# 2svd.net
KiCad netlist of a schematic drawn in EAGLE
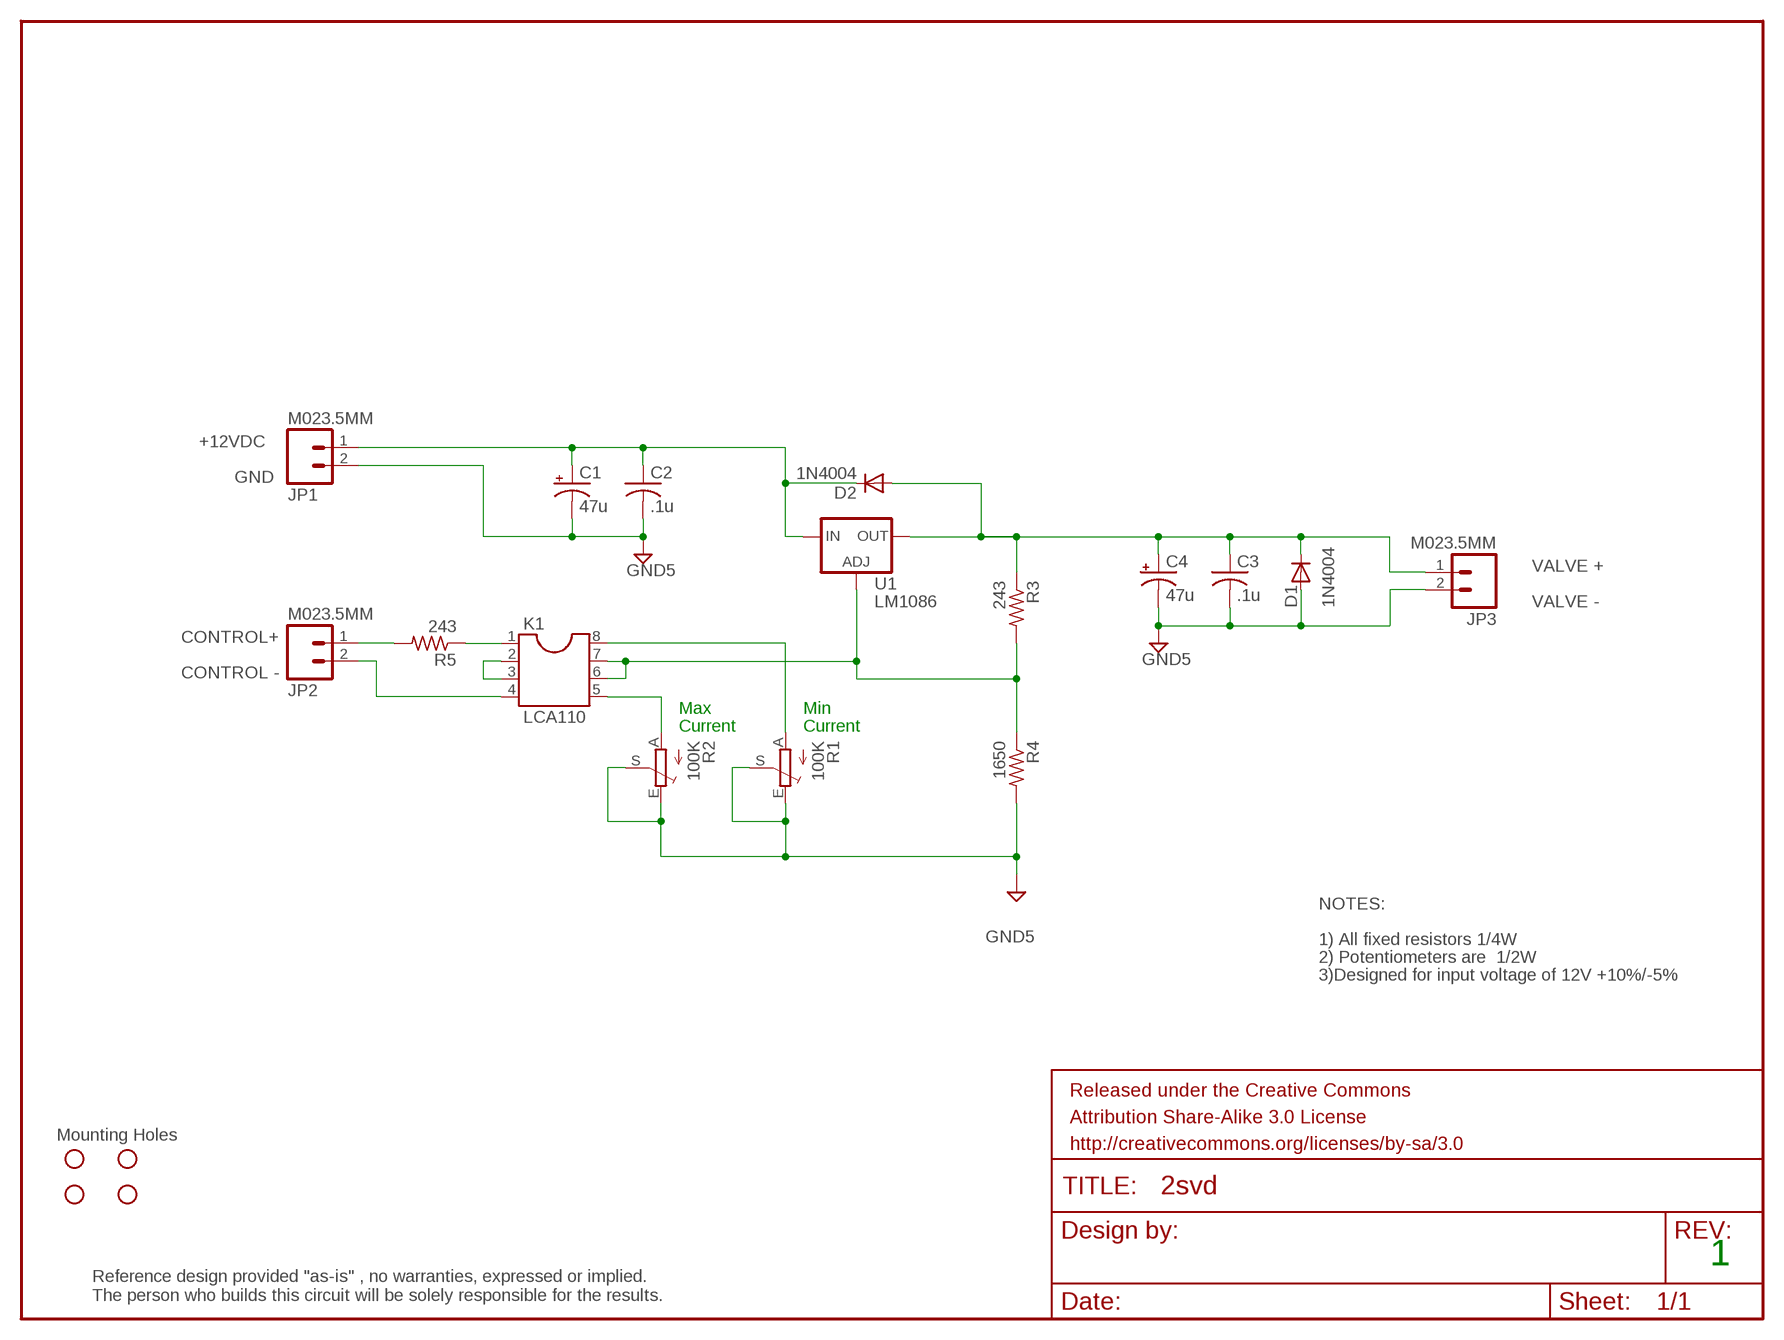
[diagram p0: schematic, sheet 1]

(export (version "E")
  (design (tool "Eeschema 10.0.6"))
  (components
    (comp (ref "C1")
      (value "47u")
      (footprint "eagle-import:CPOL-RADIAL-10UF-25V")
      (libsource (lib "eagle-import") (part "CAP_POLPTH2"))
    )
    (comp (ref "C2")
      (value ".1u")
      (footprint "eagle-import:C075-032X103")
      (libsource (lib "eagle-import") (part "C-US075-032X103"))
    )
    (comp (ref "C3")
      (value ".1u")
      (footprint "eagle-import:C075-032X103")
      (libsource (lib "eagle-import") (part "C-US075-032X103"))
    )
    (comp (ref "C4")
      (value "47u")
      (footprint "eagle-import:CPOL-RADIAL-10UF-25V")
      (libsource (lib "eagle-import") (part "CAP_POLPTH2"))
    )
    (comp (ref "D1")
      (value "1N4004")
      (footprint "eagle-import:DO41-10")
      (libsource (lib "eagle-import") (part "1N4004"))
    )
    (comp (ref "D2")
      (value "1N4004")
      (footprint "eagle-import:DO41-10")
      (libsource (lib "eagle-import") (part "1N4004"))
    )
    (comp (ref "FRAME1")
      (value "FRAME-LETTER")
      (footprint "eagle-import:CREATIVE_COMMONS")
      (libsource (lib "eagle-import") (part "FRAME-LETTER"))
    )
    (comp (ref "H1")
      (value "STAND-OFF")
      (footprint "eagle-import:STAND-OFF")
      (libsource (lib "eagle-import") (part "STAND-OFF"))
    )
    (comp (ref "H2")
      (value "STAND-OFF")
      (footprint "eagle-import:STAND-OFF")
      (libsource (lib "eagle-import") (part "STAND-OFF"))
    )
    (comp (ref "H3")
      (value "STAND-OFF")
      (footprint "eagle-import:STAND-OFF")
      (libsource (lib "eagle-import") (part "STAND-OFF"))
    )
    (comp (ref "H4")
      (value "STAND-OFF")
      (footprint "eagle-import:STAND-OFF")
      (libsource (lib "eagle-import") (part "STAND-OFF"))
    )
    (comp (ref "JP1")
      (value "M023.5MM")
      (footprint "eagle-import:SCREWTERMINAL-3.5MM-2")
      (libsource (lib "eagle-import") (part "M023.5MM"))
    )
    (comp (ref "JP2")
      (value "M023.5MM")
      (footprint "eagle-import:SCREWTERMINAL-3.5MM-2")
      (libsource (lib "eagle-import") (part "M023.5MM"))
    )
    (comp (ref "JP3")
      (value "M023.5MM")
      (footprint "eagle-import:SCREWTERMINAL-3.5MM-2")
      (libsource (lib "eagle-import") (part "M023.5MM"))
    )
    (comp (ref "K1")
      (value "LCA110")
      (footprint "eagle-import:DIL08")
      (libsource (lib "eagle-import") (part "DIL8"))
    )
    (comp (ref "R1")
      (value "100K")
      (footprint "eagle-import:RJ9W")
      (libsource (lib "eagle-import") (part "TRIM_EU-RJ9W"))
    )
    (comp (ref "R2")
      (value "100K")
      (footprint "eagle-import:RJ9W")
      (libsource (lib "eagle-import") (part "TRIM_EU-RJ9W"))
    )
    (comp (ref "R3")
      (value "243")
      (footprint "eagle-import:0207_10")
      (libsource (lib "eagle-import") (part "R-US_0207/10"))
    )
    (comp (ref "R4")
      (value "1650")
      (footprint "eagle-import:0207_10")
      (libsource (lib "eagle-import") (part "R-US_0207/10"))
    )
    (comp (ref "R5")
      (value "243")
      (footprint "eagle-import:0207_10")
      (libsource (lib "eagle-import") (part "R-US_0207/10"))
    )
    (comp (ref "U1")
      (value "LM1086")
      (footprint "eagle-import:317TS")
      (libsource (lib "eagle-import") (part "LM317TS"))
    )
  )
  (nets
    (net (code "1") (name "GND5") (class "Default")
      (node (ref "C1") (pin "2") (pinfunction "-_2") (pintype "passive"))
      (node (ref "C2") (pin "2") (pinfunction "2_2") (pintype "passive"))
      (node (ref "C3") (pin "2") (pinfunction "2_2") (pintype "passive"))
      (node (ref "C4") (pin "2") (pinfunction "-_2") (pintype "passive"))
      (node (ref "D1") (pin "A") (pinfunction "A_A") (pintype "passive"))
      (node (ref "JP1") (pin "2") (pinfunction "2_2") (pintype "passive"))
      (node (ref "JP3") (pin "2") (pinfunction "2_2") (pintype "passive"))
      (node (ref "R1") (pin "E") (pinfunction "E_E") (pintype "passive"))
      (node (ref "R1") (pin "S") (pinfunction "S_S") (pintype "passive"))
      (node (ref "R2") (pin "E") (pinfunction "E_E") (pintype "passive"))
      (node (ref "R2") (pin "S") (pinfunction "S_S") (pintype "passive"))
      (node (ref "R4") (pin "2") (pinfunction "2_2") (pintype "passive"))
    )
    (net (code "2") (name "Net-(C1-+)") (class "Default")
      (node (ref "C1") (pin "1") (pinfunction "+_1") (pintype "passive"))
      (node (ref "C2") (pin "1") (pinfunction "1_1") (pintype "passive"))
      (node (ref "D2") (pin "C") (pinfunction "C_C") (pintype "passive"))
      (node (ref "JP1") (pin "1") (pinfunction "1_1") (pintype "passive"))
      (node (ref "U1") (pin "3") (pinfunction "IN_3") (pintype "input"))
    )
    (net (code "3") (name "Net-(C4-+)") (class "Default")
      (node (ref "C3") (pin "1") (pinfunction "1_1") (pintype "passive"))
      (node (ref "C4") (pin "1") (pinfunction "+_1") (pintype "passive"))
      (node (ref "D1") (pin "C") (pinfunction "C_C") (pintype "passive"))
      (node (ref "D2") (pin "A") (pinfunction "A_A") (pintype "passive"))
      (node (ref "JP3") (pin "1") (pinfunction "1_1") (pintype "passive"))
      (node (ref "R3") (pin "1") (pinfunction "1_1") (pintype "passive"))
      (node (ref "U1") (pin "2") (pinfunction "OUT_2") (pintype "passive"))
    )
    (net (code "4") (name "Net-(JP2-Pad1)") (class "Default")
      (node (ref "JP2") (pin "1") (pinfunction "1_1") (pintype "passive"))
      (node (ref "R5") (pin "2") (pinfunction "2_2") (pintype "passive"))
    )
    (net (code "5") (name "Net-(JP2-Pad2)") (class "Default")
      (node (ref "JP2") (pin "2") (pinfunction "2_2") (pintype "passive"))
      (node (ref "K1") (pin "4") (pinfunction "4_4") (pintype "passive"))
    )
    (net (code "6") (name "Net-(K1-Pad1)") (class "Default")
      (node (ref "K1") (pin "1") (pinfunction "1_1") (pintype "passive"))
      (node (ref "R5") (pin "1") (pinfunction "1_1") (pintype "passive"))
    )
    (net (code "7") (name "Net-(K1-Pad2)") (class "Default")
      (node (ref "K1") (pin "2") (pinfunction "2_2") (pintype "passive"))
      (node (ref "K1") (pin "3") (pinfunction "3_3") (pintype "passive"))
    )
    (net (code "8") (name "Net-(K1-Pad5)") (class "Default")
      (node (ref "K1") (pin "5") (pinfunction "5_5") (pintype "passive"))
      (node (ref "R2") (pin "A") (pinfunction "A_A") (pintype "passive"))
    )
    (net (code "9") (name "Net-(K1-Pad8)") (class "Default")
      (node (ref "K1") (pin "8") (pinfunction "8_8") (pintype "passive"))
      (node (ref "R1") (pin "A") (pinfunction "A_A") (pintype "passive"))
    )
    (net (code "10") (name "Net-(U1-ADJ)") (class "Default")
      (node (ref "K1") (pin "6") (pinfunction "6_6") (pintype "passive"))
      (node (ref "K1") (pin "7") (pinfunction "7_7") (pintype "passive"))
      (node (ref "R3") (pin "2") (pinfunction "2_2") (pintype "passive"))
      (node (ref "R4") (pin "1") (pinfunction "1_1") (pintype "passive"))
      (node (ref "U1") (pin "1") (pinfunction "ADJ_1") (pintype "input"))
    )
  )
)
